# what-the-frequency-mk-2.net
KiCad netlist of a schematic drawn in EAGLE
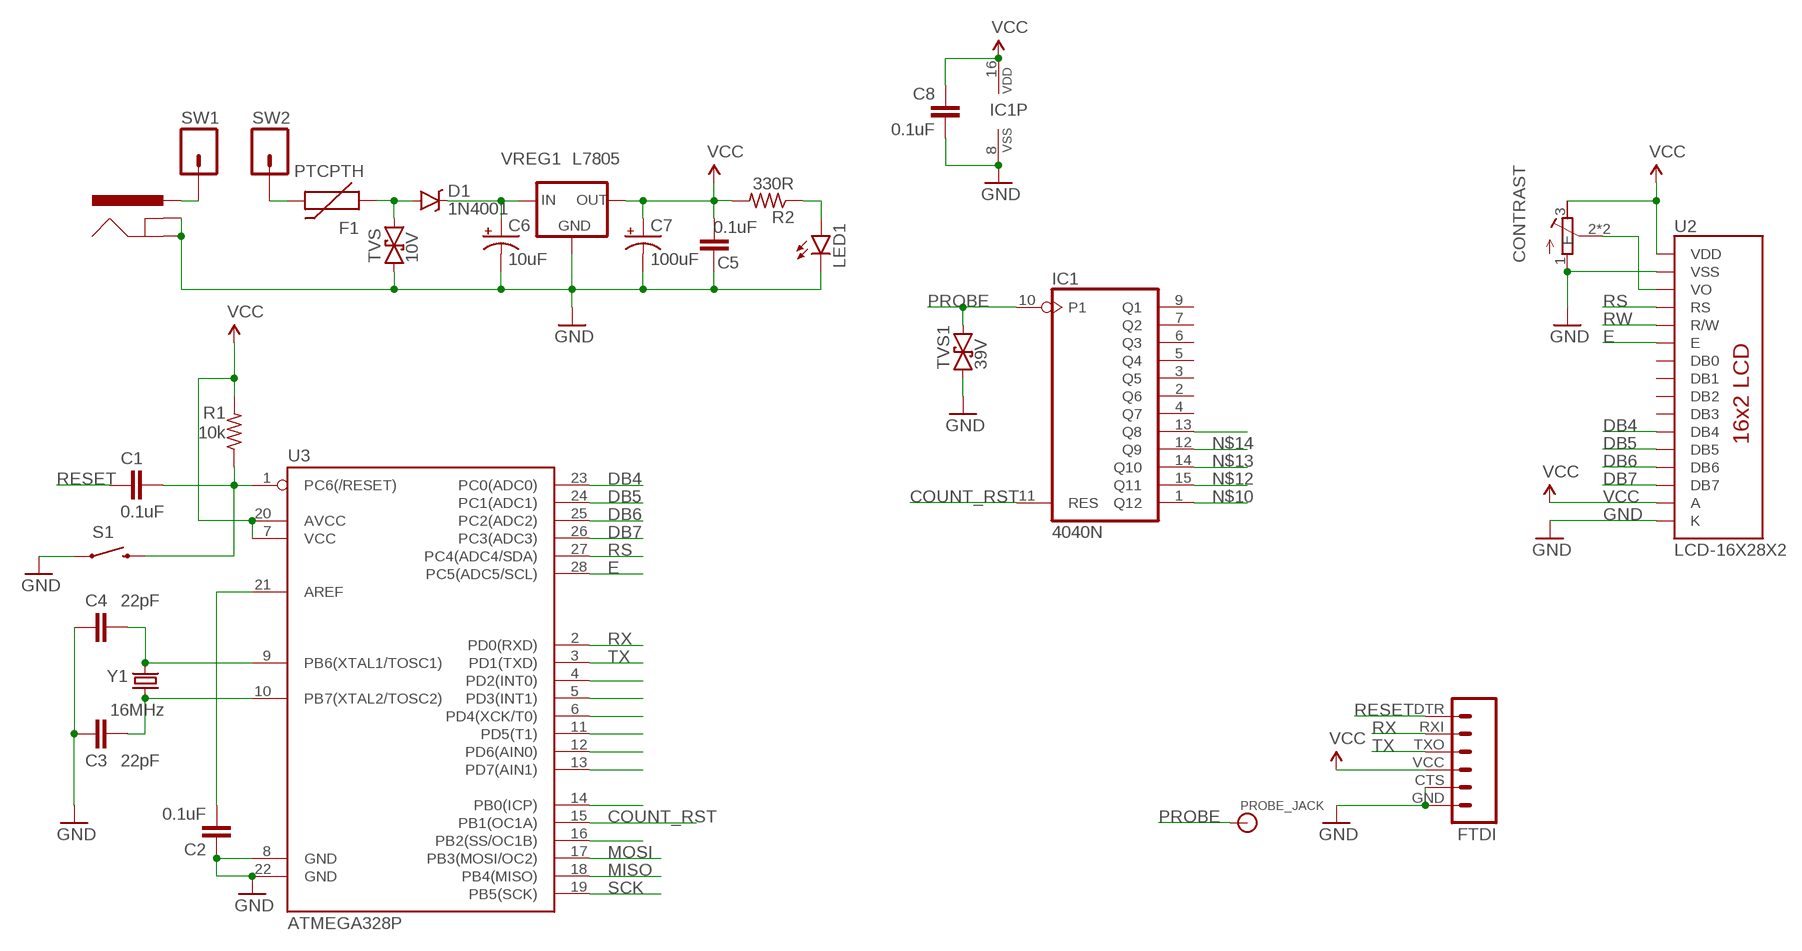
[diagram p0: schematic, sheet 1]

(export (version "E")
  (design (tool "Eeschema 10.0.6"))
  (components
    (comp (ref "C1")
      (value "0.1uF")
      (footprint "eagle-import:C025-024X044")
      (libsource (lib "eagle-import") (part "CAPACITOR-CERAMIC025-024X044"))
    )
    (comp (ref "C2")
      (value "0.1uF")
      (footprint "eagle-import:C025-024X044")
      (libsource (lib "eagle-import") (part "CAPACITOR-CERAMIC025-024X044"))
    )
    (comp (ref "C3")
      (value "22pF")
      (footprint "eagle-import:C025-024X044")
      (libsource (lib "eagle-import") (part "CAPACITOR-CERAMIC025-024X044"))
    )
    (comp (ref "C4")
      (value "22pF")
      (footprint "eagle-import:C025-024X044")
      (libsource (lib "eagle-import") (part "CAPACITOR-CERAMIC025-024X044"))
    )
    (comp (ref "C5")
      (value "0.1uF")
      (footprint "eagle-import:C025-024X044")
      (libsource (lib "eagle-import") (part "CAPACITOR-CERAMIC025-024X044"))
    )
    (comp (ref "C6")
      (value "10uF")
      (footprint "eagle-import:E2,5-5")
      (libsource (lib "eagle-import") (part "CAPACITOR-POLARIZEDE2.5-5"))
    )
    (comp (ref "C7")
      (value "100uF")
      (footprint "eagle-import:E2,5-5")
      (libsource (lib "eagle-import") (part "CAPACITOR-POLARIZEDE2.5-5"))
    )
    (comp (ref "C8")
      (value "0.1uF")
      (footprint "eagle-import:C025-024X044")
      (libsource (lib "eagle-import") (part "CAPACITOR-CERAMIC025-024X044"))
    )
    (comp (ref "CONTRAST")
      (value "POTENTIOMETERTHUMBWHEEL-16MM")
      (footprint "eagle-import:POT-THUMBWHEEL")
      (libsource (lib "eagle-import") (part "POTENTIOMETERTHUMBWHEEL-16MM"))
    )
    (comp (ref "D1")
      (value "1N4001")
      (footprint "eagle-import:DO-41")
      (libsource (lib "eagle-import") (part "DIODE-SCHOTTKYDO-41"))
    )
    (comp (ref "F1")
      (value "PTCPTH")
      (footprint "eagle-import:PTC")
      (libsource (lib "eagle-import") (part "PTCPTH"))
    )
    (comp (ref "FTDI")
      (value "FTDI_BASICPTH-TINY-TEXT")
      (footprint "eagle-import:FTDI_TINY_TXT")
      (libsource (lib "eagle-import") (part "FTDI_BASICPTH-TINY-TEXT"))
    )
    (comp (ref "IC1")
      (value "4040N")
      (footprint "eagle-import:DIL16")
      (libsource (lib "eagle-import") (part "4040N"))
    )
    (comp (ref "J1")
      (value "POWER_JACKPTH")
      (footprint "eagle-import:POWER_JACK_PTH")
      (libsource (lib "eagle-import") (part "POWER_JACKPTH"))
    )
    (comp (ref "LED1")
      (value "LED3MM")
      (footprint "eagle-import:LED3MM")
      (libsource (lib "eagle-import") (part "LED3MM"))
    )
    (comp (ref "PROBE_JACK")
      (value "BANANA_CONNPTH-RA")
      (footprint "eagle-import:BANANA-PTH-RA-SAFEWORD")
      (libsource (lib "eagle-import") (part "BANANA_CONNPTH-RA"))
    )
    (comp (ref "R1")
      (value "10k")
      (footprint "eagle-import:AXIAL-PTH-5.08MM")
      (libsource (lib "eagle-import") (part "RESISTORPTH-AXIAL-5.08MM"))
    )
    (comp (ref "R2")
      (value "330R")
      (footprint "eagle-import:AXIAL-PTH-5.08MM")
      (libsource (lib "eagle-import") (part "RESISTORPTH-AXIAL-5.08MM"))
    )
    (comp (ref "S1")
      (value "SWITCH-MOMENTARY-2PTH-RA")
      (footprint "eagle-import:TACTILE-PTH-SIDE")
      (libsource (lib "eagle-import") (part "SWITCH-MOMENTARY-2PTH-RA"))
    )
    (comp (ref "SW1")
      (value "M01PTH_2MM")
      (footprint "eagle-import:1X01_2MM")
      (libsource (lib "eagle-import") (part "M01PTH_2MM"))
    )
    (comp (ref "SW2")
      (value "M01PTH_2MM")
      (footprint "eagle-import:1X01_2MM")
      (libsource (lib "eagle-import") (part "M01PTH_2MM"))
    )
    (comp (ref "TVS")
      (value "10V")
      (footprint "eagle-import:DO-41-TVS")
      (libsource (lib "eagle-import") (part "TVSDO-41-TVS-BIDIRECTIONAL"))
    )
    (comp (ref "TVS1")
      (value "39V")
      (footprint "eagle-import:DO-41-TVS")
      (libsource (lib "eagle-import") (part "TVSDO-41-TVS-BIDIRECTIONAL"))
    )
    (comp (ref "U2")
      (value "LCD-16X28X2")
      (footprint "eagle-import:LCD-8X2")
      (libsource (lib "eagle-import") (part "LCD-16X28X2"))
    )
    (comp (ref "U3")
      (value "ATMEGA328P")
      (footprint "eagle-import:DIL28-3")
      (libsource (lib "eagle-import") (part "ATMEGA328P_PDIP"))
    )
    (comp (ref "VREG1")
      (value "L7805")
      (footprint "eagle-import:TO-92-AMMO")
      (libsource (lib "eagle-import") (part "V_REG_78XXTO-92-INLINE"))
    )
    (comp (ref "Y1")
      (value "16MHz")
      (footprint "eagle-import:HC49U-V")
      (libsource (lib "eagle-import") (part "CRYSTALHC49UV"))
    )
  )
  (nets
    (net (code "1") (name "/COUNT_RST") (class "Default")
      (node (ref "IC1") (pin "11") (pinfunction "RES_11") (pintype "input"))
      (node (ref "U3") (pin "15") (pinfunction "PB1(OC1A)_15") (pintype "bidirectional"))
    )
    (net (code "2") (name "/DB4") (class "Default")
      (node (ref "U2") (pin "11") (pinfunction "DB4_11") (pintype "bidirectional"))
      (node (ref "U3") (pin "23") (pinfunction "PC0(ADC0)_23") (pintype "bidirectional"))
    )
    (net (code "3") (name "/DB5") (class "Default")
      (node (ref "U2") (pin "12") (pinfunction "DB5_12") (pintype "bidirectional"))
      (node (ref "U3") (pin "24") (pinfunction "PC1(ADC1)_24") (pintype "bidirectional"))
    )
    (net (code "4") (name "/DB6") (class "Default")
      (node (ref "U2") (pin "13") (pinfunction "DB6_13") (pintype "bidirectional"))
      (node (ref "U3") (pin "25") (pinfunction "PC2(ADC2)_25") (pintype "bidirectional"))
    )
    (net (code "5") (name "/DB7") (class "Default")
      (node (ref "U2") (pin "14") (pinfunction "DB7_14") (pintype "bidirectional"))
      (node (ref "U3") (pin "26") (pinfunction "PC3(ADC3)_26") (pintype "bidirectional"))
    )
    (net (code "6") (name "/E") (class "Default")
      (node (ref "U2") (pin "6") (pinfunction "E_6") (pintype "input"))
      (node (ref "U3") (pin "28") (pinfunction "PC5(ADC5/SCL)_28") (pintype "bidirectional"))
    )
    (net (code "7") (name "/MISO") (class "Default")
      (node (ref "U3") (pin "18") (pinfunction "PB4(MISO)_18") (pintype "bidirectional"))
    )
    (net (code "8") (name "/MOSI") (class "Default")
      (node (ref "U3") (pin "17") (pinfunction "PB3(MOSI/OC2)_17") (pintype "bidirectional"))
    )
    (net (code "9") (name "/N$10") (class "Default")
      (node (ref "IC1") (pin "1") (pinfunction "Q12_1") (pintype "output"))
    )
    (net (code "10") (name "/N$12") (class "Default")
      (node (ref "IC1") (pin "15") (pinfunction "Q11_15") (pintype "output"))
    )
    (net (code "11") (name "/N$13") (class "Default")
      (node (ref "IC1") (pin "14") (pinfunction "Q10_14") (pintype "output"))
    )
    (net (code "12") (name "/N$14") (class "Default")
      (node (ref "IC1") (pin "12") (pinfunction "Q9_12") (pintype "output"))
    )
    (net (code "13") (name "/PROBE") (class "Default")
      (node (ref "IC1") (pin "10") (pinfunction "P1_10") (pintype "input"))
      (node (ref "PROBE_JACK") (pin "P$1") (pinfunction "1_P$1") (pintype "passive"))
      (node (ref "PROBE_JACK") (pin "P$2") (pinfunction "1_P$2") (pintype "passive"))
      (node (ref "TVS1") (pin "P$2") (pinfunction "2_P$2") (pintype "passive"))
    )
    (net (code "14") (name "/RESET") (class "Default")
      (node (ref "C1") (pin "1") (pinfunction "1_1") (pintype "passive"))
      (node (ref "FTDI") (pin "DTR") (pinfunction "1_DTR") (pintype "passive"))
    )
    (net (code "15") (name "/RS") (class "Default")
      (node (ref "U2") (pin "4") (pinfunction "RS_4") (pintype "input"))
      (node (ref "U3") (pin "27") (pinfunction "PC4(ADC4/SDA)_27") (pintype "bidirectional"))
    )
    (net (code "16") (name "/RW") (class "Default")
      (node (ref "U2") (pin "5") (pinfunction "R/W_5") (pintype "input"))
    )
    (net (code "17") (name "/RX") (class "Default")
      (node (ref "FTDI") (pin "RXI") (pinfunction "2_RXI") (pintype "passive"))
      (node (ref "U3") (pin "2") (pinfunction "PD0(RXD)_2") (pintype "bidirectional"))
    )
    (net (code "18") (name "/SCK") (class "Default")
      (node (ref "U3") (pin "19") (pinfunction "PB5(SCK)_19") (pintype "bidirectional"))
    )
    (net (code "19") (name "/TX") (class "Default")
      (node (ref "FTDI") (pin "TXO") (pinfunction "3_TXO") (pintype "passive"))
      (node (ref "U3") (pin "3") (pinfunction "PD1(TXD)_3") (pintype "bidirectional"))
    )
    (net (code "20") (name "GND") (class "Default")
      (node (ref "C2") (pin "1") (pinfunction "1_1") (pintype "passive"))
      (node (ref "C3") (pin "2") (pinfunction "2_2") (pintype "passive"))
      (node (ref "C4") (pin "2") (pinfunction "2_2") (pintype "passive"))
      (node (ref "C5") (pin "1") (pinfunction "1_1") (pintype "passive"))
      (node (ref "C6") (pin "-") (pinfunction "-_-") (pintype "passive"))
      (node (ref "C7") (pin "-") (pinfunction "-_-") (pintype "passive"))
      (node (ref "C8") (pin "1") (pinfunction "1_1") (pintype "passive"))
      (node (ref "CONTRAST") (pin "1") (pinfunction "A_1") (pintype "passive"))
      (node (ref "FTDI") (pin "CTS") (pinfunction "5_CTS") (pintype "passive"))
      (node (ref "FTDI") (pin "GND") (pinfunction "6_GND") (pintype "passive"))
      (node (ref "IC1") (pin "8") (pinfunction "VSS_8") (pintype "power_in"))
      (node (ref "J1") (pin "GND") (pinfunction "GND_GND") (pintype "bidirectional"))
      (node (ref "J1") (pin "GNDBREAK") (pinfunction "GNDBREAK_GNDBREAK") (pintype "bidirectional"))
      (node (ref "LED1") (pin "K") (pinfunction "C_K") (pintype "passive"))
      (node (ref "S1") (pin "1") (pinfunction "1_1") (pintype "passive"))
      (node (ref "TVS") (pin "P$1") (pinfunction "1_P$1") (pintype "passive"))
      (node (ref "TVS1") (pin "P$1") (pinfunction "1_P$1") (pintype "passive"))
      (node (ref "U2") (pin "1") (pinfunction "VSS_1") (pintype "power_in"))
      (node (ref "U2") (pin "16") (pinfunction "K_16") (pintype "power_in"))
      (node (ref "U3") (pin "22") (pinfunction "GND_22") (pintype "bidirectional"))
      (node (ref "U3") (pin "8") (pinfunction "GND_8") (pintype "bidirectional"))
      (node (ref "VREG1") (pin "2") (pinfunction "GND_2") (pintype "input"))
    )
    (net (code "21") (name "Net-(F1-1)") (class "Default")
      (node (ref "D1") (pin "A") (pinfunction "A_A") (pintype "passive"))
      (node (ref "F1") (pin "P$1") (pinfunction "1_P$1") (pintype "bidirectional"))
      (node (ref "TVS") (pin "P$2") (pinfunction "2_P$2") (pintype "passive"))
    )
    (net (code "22") (name "Net-(F1-2)") (class "Default")
      (node (ref "F1") (pin "P$2") (pinfunction "2_P$2") (pintype "bidirectional"))
      (node (ref "SW2") (pin "1") (pinfunction "1_1") (pintype "passive"))
    )
    (net (code "23") (name "Net-(J1-PadPWR)") (class "Default")
      (node (ref "J1") (pin "PWR") (pinfunction "PWR_PWR") (pintype "bidirectional"))
      (node (ref "SW1") (pin "1") (pinfunction "1_1") (pintype "passive"))
    )
    (net (code "24") (name "Net-(R1-1)") (class "Default")
      (node (ref "C1") (pin "2") (pinfunction "2_2") (pintype "passive"))
      (node (ref "R1") (pin "P$1") (pinfunction "1_P$1") (pintype "passive"))
      (node (ref "S1") (pin "2") (pinfunction "2_2") (pintype "passive"))
      (node (ref "U3") (pin "1") (pinfunction "PC6(/RESET)_1") (pintype "bidirectional"))
    )
    (net (code "25") (name "Net-(R2-1)") (class "Default")
      (node (ref "LED1") (pin "A") (pinfunction "A_A") (pintype "passive"))
      (node (ref "R2") (pin "P$1") (pinfunction "1_P$1") (pintype "passive"))
    )
    (net (code "26") (name "Net-(U2-VO)") (class "Default")
      (node (ref "CONTRAST") (pin "2") (pinfunction "S_2") (pintype "passive"))
      (node (ref "CONTRAST") (pin "2@1") (pinfunction "S_2@1") (pintype "passive"))
      (node (ref "U2") (pin "3") (pinfunction "VO_3") (pintype "bidirectional"))
    )
    (net (code "27") (name "Net-(U3-AREF)") (class "Default")
      (node (ref "C2") (pin "2") (pinfunction "2_2") (pintype "passive"))
      (node (ref "U3") (pin "21") (pinfunction "AREF_21") (pintype "bidirectional"))
    )
    (net (code "28") (name "Net-(U3-PB6(XTAL1{slash}TOSC1))") (class "Default")
      (node (ref "C4") (pin "1") (pinfunction "1_1") (pintype "passive"))
      (node (ref "U3") (pin "9") (pinfunction "PB6(XTAL1/TOSC1)_9") (pintype "bidirectional"))
      (node (ref "Y1") (pin "2") (pinfunction "2_2") (pintype "passive"))
    )
    (net (code "29") (name "Net-(U3-PB7(XTAL2{slash}TOSC2))") (class "Default")
      (node (ref "C3") (pin "1") (pinfunction "1_1") (pintype "passive"))
      (node (ref "U3") (pin "10") (pinfunction "PB7(XTAL2/TOSC2)_10") (pintype "bidirectional"))
      (node (ref "Y1") (pin "1") (pinfunction "1_1") (pintype "passive"))
    )
    (net (code "30") (name "Net-(VREG1-IN)") (class "Default")
      (node (ref "C6") (pin "+") (pinfunction "+_+") (pintype "passive"))
      (node (ref "D1") (pin "C") (pinfunction "C_C") (pintype "passive"))
      (node (ref "VREG1") (pin "1") (pinfunction "IN_1") (pintype "input"))
    )
    (net (code "31") (name "VCC") (class "Default")
      (node (ref "C5") (pin "2") (pinfunction "2_2") (pintype "passive"))
      (node (ref "C7") (pin "+") (pinfunction "+_+") (pintype "passive"))
      (node (ref "C8") (pin "2") (pinfunction "2_2") (pintype "passive"))
      (node (ref "CONTRAST") (pin "3") (pinfunction "E_3") (pintype "passive"))
      (node (ref "FTDI") (pin "VCC") (pinfunction "4_VCC") (pintype "passive"))
      (node (ref "IC1") (pin "16") (pinfunction "VDD_16") (pintype "power_in"))
      (node (ref "R1") (pin "P$2") (pinfunction "2_P$2") (pintype "passive"))
      (node (ref "R2") (pin "P$2") (pinfunction "2_P$2") (pintype "passive"))
      (node (ref "U2") (pin "15") (pinfunction "A_15") (pintype "power_in"))
      (node (ref "U2") (pin "2") (pinfunction "VDD_2") (pintype "power_in"))
      (node (ref "U3") (pin "20") (pinfunction "AVCC_20") (pintype "bidirectional"))
      (node (ref "U3") (pin "7") (pinfunction "VCC_7") (pintype "bidirectional"))
      (node (ref "VREG1") (pin "3") (pinfunction "OUT_3") (pintype "output"))
    )
    (net (code "32") (name "unconnected-(IC1A-Q1-Pad9)") (class "Default")
      (node (ref "IC1") (pin "9") (pinfunction "Q1_9") (pintype "output"))
    )
    (net (code "33") (name "unconnected-(IC1A-Q2-Pad7)") (class "Default")
      (node (ref "IC1") (pin "7") (pinfunction "Q2_7") (pintype "output"))
    )
    (net (code "34") (name "unconnected-(IC1A-Q3-Pad6)") (class "Default")
      (node (ref "IC1") (pin "6") (pinfunction "Q3_6") (pintype "output"))
    )
    (net (code "35") (name "unconnected-(IC1A-Q4-Pad5)") (class "Default")
      (node (ref "IC1") (pin "5") (pinfunction "Q4_5") (pintype "output"))
    )
    (net (code "36") (name "unconnected-(IC1A-Q5-Pad3)") (class "Default")
      (node (ref "IC1") (pin "3") (pinfunction "Q5_3") (pintype "output"))
    )
    (net (code "37") (name "unconnected-(IC1A-Q6-Pad2)") (class "Default")
      (node (ref "IC1") (pin "2") (pinfunction "Q6_2") (pintype "output"))
    )
    (net (code "38") (name "unconnected-(IC1A-Q7-Pad4)") (class "Default")
      (node (ref "IC1") (pin "4") (pinfunction "Q7_4") (pintype "output"))
    )
    (net (code "39") (name "unconnected-(IC1A-Q8-Pad13)") (class "Default")
      (node (ref "IC1") (pin "13") (pinfunction "Q8_13") (pintype "output"))
    )
    (net (code "40") (name "unconnected-(U2-DB0-Pad7)") (class "Default")
      (node (ref "U2") (pin "7") (pinfunction "DB0_7") (pintype "bidirectional"))
    )
    (net (code "41") (name "unconnected-(U2-DB1-Pad8)") (class "Default")
      (node (ref "U2") (pin "8") (pinfunction "DB1_8") (pintype "bidirectional"))
    )
    (net (code "42") (name "unconnected-(U2-DB2-Pad9)") (class "Default")
      (node (ref "U2") (pin "9") (pinfunction "DB2_9") (pintype "bidirectional"))
    )
    (net (code "43") (name "unconnected-(U2-DB3-Pad10)") (class "Default")
      (node (ref "U2") (pin "10") (pinfunction "DB3_10") (pintype "bidirectional"))
    )
    (net (code "44") (name "unconnected-(U3-PB0(ICP)-Pad14)") (class "Default")
      (node (ref "U3") (pin "14") (pinfunction "PB0(ICP)_14") (pintype "bidirectional"))
    )
    (net (code "45") (name "unconnected-(U3-PB2(SS{slash}OC1B)-Pad16)") (class "Default")
      (node (ref "U3") (pin "16") (pinfunction "PB2(SS/OC1B)_16") (pintype "bidirectional"))
    )
    (net (code "46") (name "unconnected-(U3-PD2(INT0)-Pad4)") (class "Default")
      (node (ref "U3") (pin "4") (pinfunction "PD2(INT0)_4") (pintype "bidirectional"))
    )
    (net (code "47") (name "unconnected-(U3-PD3(INT1)-Pad5)") (class "Default")
      (node (ref "U3") (pin "5") (pinfunction "PD3(INT1)_5") (pintype "bidirectional"))
    )
    (net (code "48") (name "unconnected-(U3-PD4(XCK{slash}T0)-Pad6)") (class "Default")
      (node (ref "U3") (pin "6") (pinfunction "PD4(XCK/T0)_6") (pintype "bidirectional"))
    )
    (net (code "49") (name "unconnected-(U3-PD5(T1)-Pad11)") (class "Default")
      (node (ref "U3") (pin "11") (pinfunction "PD5(T1)_11") (pintype "bidirectional"))
    )
    (net (code "50") (name "unconnected-(U3-PD6(AIN0)-Pad12)") (class "Default")
      (node (ref "U3") (pin "12") (pinfunction "PD6(AIN0)_12") (pintype "bidirectional"))
    )
    (net (code "51") (name "unconnected-(U3-PD7(AIN1)-Pad13)") (class "Default")
      (node (ref "U3") (pin "13") (pinfunction "PD7(AIN1)_13") (pintype "bidirectional"))
    )
  )
)
